# -V1.net
KiCad netlist of a schematic drawn in Altium Designer
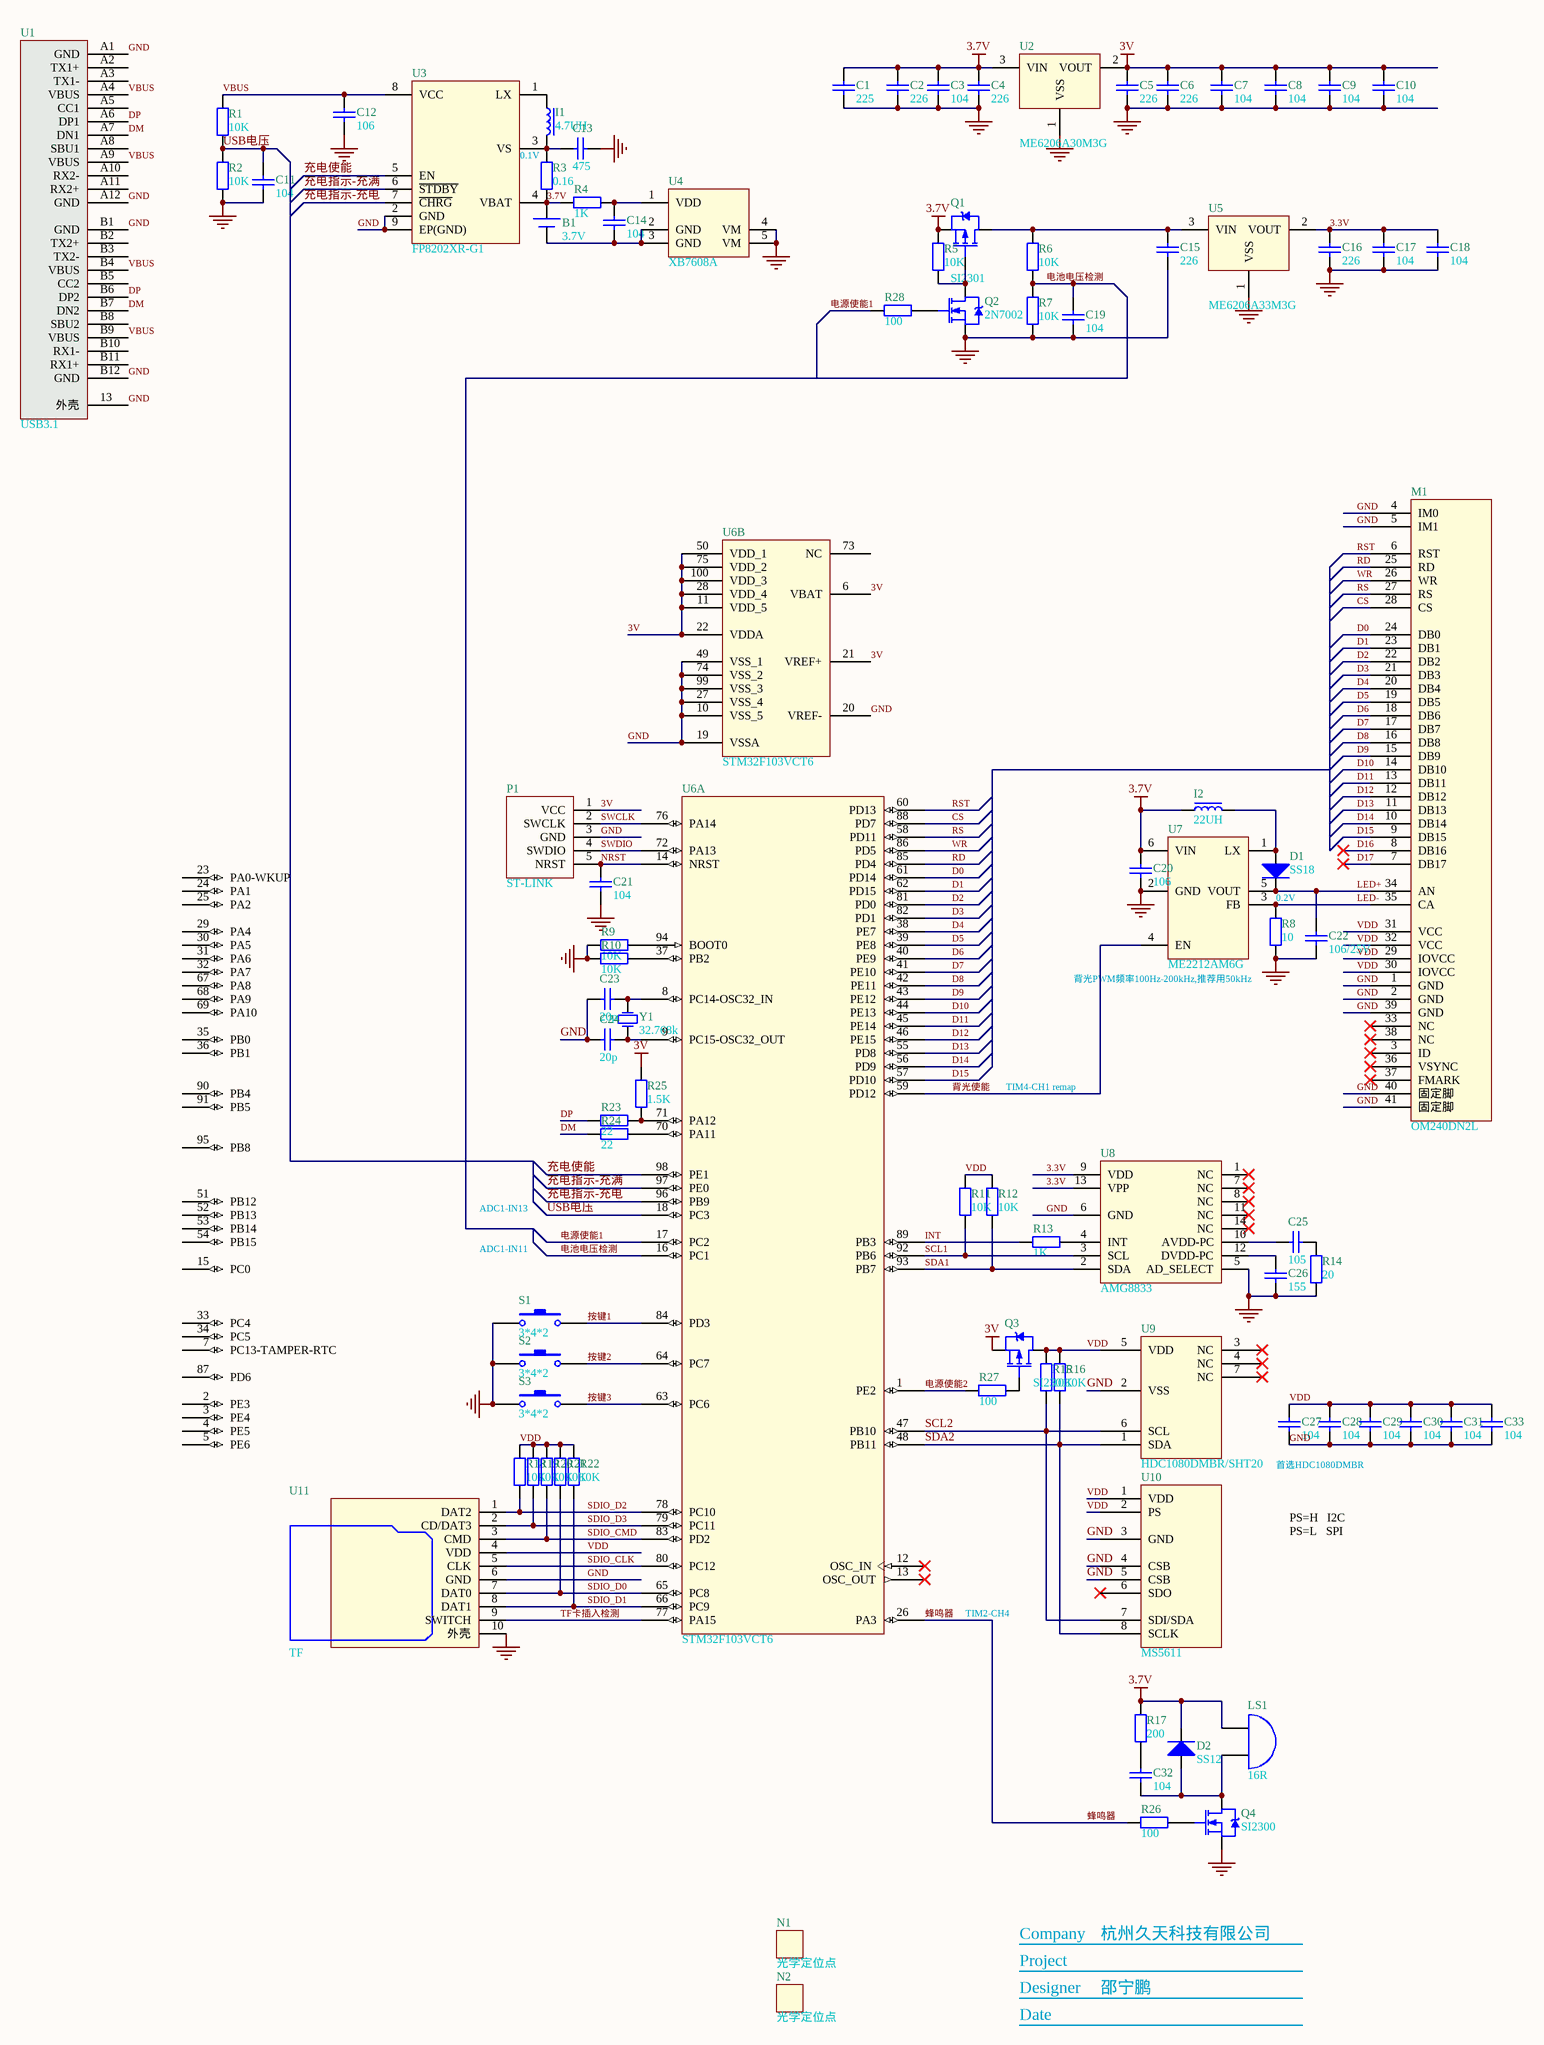
[diagram p0: 红外热像仪-V1.SchDoc]

(export (version "E")
  (design (tool "Eeschema 10.0.6"))
  (components
    (comp (ref "B1")
      (value "3.7V")
      (footprint "PH2.0-卧式贴片-2P")
      (description "锂电池")
      (libsource (lib "11其他元件-V1.0") (part "Battery1"))
    )
    (comp (ref "C1")
      (value "225")
      (footprint "C-0603")
      (description "0805")
      (fields (field (name "PUBLISHER") "Altium Limited"))
      (libsource (lib "2电容-V1.0") (part "Cap-0603"))
    )
    (comp (ref "C2")
      (value "226")
      (footprint "C-0603")
      (description "0805")
      (fields (field (name "PUBLISHER") "Altium Limited"))
      (libsource (lib "2电容-V1.0") (part "Cap-0603"))
    )
    (comp (ref "C3")
      (value "104")
      (footprint "C-0603")
      (description "0805")
      (fields (field (name "PUBLISHER") "Altium Limited"))
      (libsource (lib "2电容-V1.0") (part "Cap-0603"))
    )
    (comp (ref "C4")
      (value "226")
      (footprint "C-0603")
      (description "0805")
      (fields (field (name "PUBLISHER") "Altium Limited"))
      (libsource (lib "2电容-V1.0") (part "Cap-0603"))
    )
    (comp (ref "C5")
      (value "226")
      (footprint "C-0603")
      (description "0805")
      (fields (field (name "PUBLISHER") "Altium Limited"))
      (libsource (lib "2电容-V1.0") (part "Cap-0603"))
    )
    (comp (ref "C6")
      (value "226")
      (footprint "C-0603")
      (description "0805")
      (fields (field (name "PUBLISHER") "Altium Limited"))
      (libsource (lib "2电容-V1.0") (part "Cap-0603"))
    )
    (comp (ref "C7")
      (value "104")
      (footprint "C-0603")
      (description "0805")
      (fields (field (name "PUBLISHER") "Altium Limited"))
      (libsource (lib "2电容-V1.0") (part "Cap-0603"))
    )
    (comp (ref "C8")
      (value "104")
      (footprint "C-0603")
      (description "0805")
      (fields (field (name "PUBLISHER") "Altium Limited"))
      (libsource (lib "2电容-V1.0") (part "Cap-0603"))
    )
    (comp (ref "C9")
      (value "104")
      (footprint "C-0603")
      (description "0805")
      (fields (field (name "PUBLISHER") "Altium Limited"))
      (libsource (lib "2电容-V1.0") (part "Cap-0603"))
    )
    (comp (ref "C10")
      (value "104")
      (footprint "C-0603")
      (description "0805")
      (fields (field (name "PUBLISHER") "Altium Limited"))
      (libsource (lib "2电容-V1.0") (part "Cap-0603"))
    )
    (comp (ref "C11")
      (value "104")
      (footprint "C-0603")
      (description "0805")
      (fields (field (name "PUBLISHER") "Altium Limited"))
      (libsource (lib "2电容-V1.0") (part "Cap-0603"))
    )
    (comp (ref "C12")
      (value "106")
      (footprint "C-0603")
      (description "0805")
      (fields (field (name "PUBLISHER") "Altium Limited"))
      (libsource (lib "2电容-V1.0") (part "Cap-0603"))
    )
    (comp (ref "C13")
      (value "475")
      (footprint "C-0603")
      (description "0805")
      (fields (field (name "PUBLISHER") "Altium Limited"))
      (libsource (lib "2电容-V1.0") (part "Cap-0603"))
    )
    (comp (ref "C14")
      (value "104")
      (footprint "C-0603")
      (description "0805")
      (fields (field (name "PUBLISHER") "Altium Limited"))
      (libsource (lib "2电容-V1.0") (part "Cap-0603"))
    )
    (comp (ref "C15")
      (value "226")
      (footprint "C-0603")
      (description "0805")
      (fields (field (name "PUBLISHER") "Altium Limited"))
      (libsource (lib "2电容-V1.0") (part "Cap-0603"))
    )
    (comp (ref "C16")
      (value "226")
      (footprint "C-0603")
      (description "0805")
      (fields (field (name "PUBLISHER") "Altium Limited"))
      (libsource (lib "2电容-V1.0") (part "Cap-0603"))
    )
    (comp (ref "C17")
      (value "104")
      (footprint "C-0603")
      (description "0805")
      (fields (field (name "PUBLISHER") "Altium Limited"))
      (libsource (lib "2电容-V1.0") (part "Cap-0603"))
    )
    (comp (ref "C18")
      (value "104")
      (footprint "C-0603")
      (description "0805")
      (fields (field (name "PUBLISHER") "Altium Limited"))
      (libsource (lib "2电容-V1.0") (part "Cap-0603"))
    )
    (comp (ref "C19")
      (value "104")
      (footprint "C-0603")
      (description "0805")
      (fields (field (name "PUBLISHER") "Altium Limited"))
      (libsource (lib "2电容-V1.0") (part "Cap-0603"))
    )
    (comp (ref "C20")
      (value "106")
      (footprint "C-0603")
      (description "0805")
      (fields (field (name "PUBLISHER") "Altium Limited"))
      (libsource (lib "2电容-V1.0") (part "Cap-0603"))
    )
    (comp (ref "C21")
      (value "104")
      (footprint "C-0603")
      (description "0805")
      (fields (field (name "PUBLISHER") "Altium Limited"))
      (libsource (lib "2电容-V1.0") (part "Cap-0603"))
    )
    (comp (ref "C22")
      (value "106/25V")
      (footprint "C-0603")
      (description "0805")
      (fields (field (name "PUBLISHER") "Altium Limited"))
      (libsource (lib "2电容-V1.0") (part "Cap-0603"))
    )
    (comp (ref "C23")
      (value "20p")
      (footprint "C-0603")
      (description "0805")
      (fields (field (name "PUBLISHER") "Altium Limited"))
      (libsource (lib "2电容-V1.0") (part "Cap-0603"))
    )
    (comp (ref "C24")
      (value "20p")
      (footprint "C-0603")
      (description "0805")
      (fields (field (name "PUBLISHER") "Altium Limited"))
      (libsource (lib "2电容-V1.0") (part "Cap-0603"))
    )
    (comp (ref "C25")
      (value "105")
      (footprint "C-0603")
      (description "0805")
      (fields (field (name "PUBLISHER") "Altium Limited"))
      (libsource (lib "2电容-V1.0") (part "Cap-0603"))
    )
    (comp (ref "C26")
      (value "155")
      (footprint "C-0603")
      (description "0805")
      (fields (field (name "PUBLISHER") "Altium Limited"))
      (libsource (lib "2电容-V1.0") (part "Cap-0603"))
    )
    (comp (ref "C27")
      (value "104")
      (footprint "C-0603")
      (description "0805")
      (fields (field (name "PUBLISHER") "Altium Limited"))
      (libsource (lib "2电容-V1.0") (part "Cap-0603"))
    )
    (comp (ref "C28")
      (value "104")
      (footprint "C-0603")
      (description "0805")
      (fields (field (name "PUBLISHER") "Altium Limited"))
      (libsource (lib "2电容-V1.0") (part "Cap-0603"))
    )
    (comp (ref "C29")
      (value "104")
      (footprint "C-0603")
      (description "0805")
      (fields (field (name "PUBLISHER") "Altium Limited"))
      (libsource (lib "2电容-V1.0") (part "Cap-0603"))
    )
    (comp (ref "C30")
      (value "104")
      (footprint "C-0603")
      (description "0805")
      (fields (field (name "PUBLISHER") "Altium Limited"))
      (libsource (lib "2电容-V1.0") (part "Cap-0603"))
    )
    (comp (ref "C31")
      (value "104")
      (footprint "C-0603")
      (description "0805")
      (fields (field (name "PUBLISHER") "Altium Limited"))
      (libsource (lib "2电容-V1.0") (part "Cap-0603"))
    )
    (comp (ref "C32")
      (value "104")
      (footprint "C-0603")
      (description "0805")
      (fields (field (name "PUBLISHER") "Altium Limited"))
      (libsource (lib "2电容-V1.0") (part "Cap-0603"))
    )
    (comp (ref "C33")
      (value "104")
      (footprint "C-0603")
      (description "0805")
      (fields (field (name "PUBLISHER") "Altium Limited"))
      (libsource (lib "2电容-V1.0") (part "Cap-0603"))
    )
    (comp (ref "D1")
      (value "SS18")
      (footprint "SOD-523/0603")
      (description "SMA")
      (libsource (lib "4二极管-V1.1") (part "SS14"))
    )
    (comp (ref "D2")
      (value "SS12")
      (footprint "SOD-523/0603")
      (description "SMA")
      (libsource (lib "4二极管-V1.1") (part "SS14"))
    )
    (comp (ref "I1")
      (value "4.7UH")
      (footprint "一体成型电感0420")
      (libsource (lib "3电感-V1.0") (part "Inductance3"))
    )
    (comp (ref "I2") (value "22UH") (footprint "PRS3015") (libsource (lib "3电感-V1.0") (part "Inductance3")))
    (comp (ref "LS1")
      (value "16R")
      (footprint "蜂鸣器DET402-G-1")
      (description "Electrical Bell")
      (fields (field (name "PUBLISHER") "Altium Limited"))
      (libsource (lib "11其他元件-V1.0") (part "Bell"))
    )
    (comp (ref "M1")
      (value "OM240DN2L")
      (footprint "OM240DN2L")
      (libsource (lib "7显示屏-V1.0") (part "OM240DN2L"))
    )
    (comp (ref "N1") (value "光学定位点") (footprint "MARK-1mm-3mm") (libsource (lib "11其他元件-V1.0") (part "无引脚")))
    (comp (ref "N2") (value "光学定位点") (footprint "MARK-1mm-3mm") (libsource (lib "11其他元件-V1.0") (part "无引脚")))
    (comp (ref "P1") (value "ST-LINK") (footprint "5P下载口") (libsource (lib "下载口") (part "ST-LINK-STM32")))
    (comp (ref "Q1")
      (value "SI2301")
      (footprint "SOT-23")
      (description "SOT-23")
      (libsource (lib "4二极管-V1.1") (part "SI2301"))
    )
    (comp (ref "Q2") (value "2N7002") (footprint "SOT-23") (libsource (lib "4二极管-V1.1") (part "2N7002")))
    (comp (ref "Q3")
      (value "SI2301")
      (footprint "SOT-23")
      (description "SOT-23")
      (libsource (lib "4二极管-V1.1") (part "SI2301"))
    )
    (comp (ref "Q4") (value "SI2300") (footprint "SOT-23") (libsource (lib "4二极管-V1.1") (part "2N7002")))
    (comp (ref "R1")
      (value "10K")
      (footprint "R-0603")
      (description "0805")
      (fields (field (name "PUBLISHER") "Altium Limited"))
      (libsource (lib "") (part "Res2_2"))
    )
    (comp (ref "R2")
      (value "10K")
      (footprint "R-0603")
      (description "0805")
      (fields (field (name "PUBLISHER") "Altium Limited"))
      (libsource (lib "") (part "Res2_2"))
    )
    (comp (ref "R3")
      (value "0.16")
      (footprint "R-1206-M")
      (description "0603")
      (fields (field (name "PUBLISHER") "Altium Limited"))
      (libsource (lib "") (part "Res2-0603_2"))
    )
    (comp (ref "R4")
      (value "1K")
      (footprint "R-0603")
      (description "0603")
      (fields (field (name "PUBLISHER") "Altium Limited"))
      (libsource (lib "") (part "Res2-0603_1"))
    )
    (comp (ref "R5")
      (value "10K")
      (footprint "R-0603")
      (description "0805")
      (fields (field (name "PUBLISHER") "Altium Limited"))
      (libsource (lib "") (part "Res2_2"))
    )
    (comp (ref "R6")
      (value "10K")
      (footprint "R-0603")
      (description "0805")
      (fields (field (name "PUBLISHER") "Altium Limited"))
      (libsource (lib "") (part "Res2_1"))
    )
    (comp (ref "R7")
      (value "10K")
      (footprint "R-0603")
      (description "0805")
      (fields (field (name "PUBLISHER") "Altium Limited"))
      (libsource (lib "") (part "Res2_1"))
    )
    (comp (ref "R8")
      (value "10")
      (footprint "R-0603")
      (description "0805")
      (fields (field (name "PUBLISHER") "Altium Limited"))
      (libsource (lib "") (part "Res2_1"))
    )
    (comp (ref "R9")
      (value "10K")
      (footprint "R-0603")
      (description "0603")
      (fields (field (name "PUBLISHER") "Altium Limited"))
      (libsource (lib "") (part "Res2-0603-_3"))
    )
    (comp (ref "R10")
      (value "10K")
      (footprint "R-0603")
      (description "0603")
      (fields (field (name "PUBLISHER") "Altium Limited"))
      (libsource (lib "") (part "Res2-0603-_3"))
    )
    (comp (ref "R11")
      (value "10K")
      (footprint "R-0603")
      (description "0603")
      (fields (field (name "PUBLISHER") "Altium Limited"))
      (libsource (lib "") (part "Res2-0603-_1"))
    )
    (comp (ref "R12")
      (value "10K")
      (footprint "R-0603")
      (description "0603")
      (fields (field (name "PUBLISHER") "Altium Limited"))
      (libsource (lib "") (part "Res2-0603-_1"))
    )
    (comp (ref "R13")
      (value "1K")
      (footprint "R-0603")
      (description "0805")
      (fields (field (name "PUBLISHER") "Altium Limited"))
      (libsource (lib "1电阻-V1.0") (part "Res2"))
    )
    (comp (ref "R14")
      (value "20")
      (footprint "R-0603")
      (description "0603")
      (fields (field (name "PUBLISHER") "Altium Limited"))
      (libsource (lib "") (part "Res2-0603-_1"))
    )
    (comp (ref "R15")
      (value "10K")
      (footprint "R-0603")
      (description "0603")
      (fields (field (name "PUBLISHER") "Altium Limited"))
      (libsource (lib "") (part "Res2-0603-_2"))
    )
    (comp (ref "R16")
      (value "10K")
      (footprint "R-0603")
      (description "0603")
      (fields (field (name "PUBLISHER") "Altium Limited"))
      (libsource (lib "") (part "Res2-0603-_2"))
    )
    (comp (ref "R17")
      (value "200")
      (footprint "R-0603")
      (description "0603")
      (fields (field (name "PUBLISHER") "Altium Limited"))
      (libsource (lib "") (part "Res2-0603-_2"))
    )
    (comp (ref "R18")
      (value "10K")
      (footprint "R-0603")
      (description "0603")
      (fields (field (name "PUBLISHER") "Altium Limited"))
      (libsource (lib "1电阻-V1.0") (part "Res2-0603"))
    )
    (comp (ref "R19")
      (value "10K")
      (footprint "R-0603")
      (description "0603")
      (fields (field (name "PUBLISHER") "Altium Limited"))
      (libsource (lib "1电阻-V1.0") (part "Res2-0603"))
    )
    (comp (ref "R20")
      (value "10K")
      (footprint "R-0603")
      (description "0603")
      (fields (field (name "PUBLISHER") "Altium Limited"))
      (libsource (lib "1电阻-V1.0") (part "Res2-0603"))
    )
    (comp (ref "R21")
      (value "10K")
      (footprint "R-0603")
      (description "0603")
      (fields (field (name "PUBLISHER") "Altium Limited"))
      (libsource (lib "1电阻-V1.0") (part "Res2-0603"))
    )
    (comp (ref "R22")
      (value "10K")
      (footprint "R-0603")
      (description "0603")
      (fields (field (name "PUBLISHER") "Altium Limited"))
      (libsource (lib "1电阻-V1.0") (part "Res2-0603"))
    )
    (comp (ref "R23")
      (value "22")
      (footprint "R-0603")
      (description "0603")
      (fields (field (name "PUBLISHER") "Altium Limited"))
      (libsource (lib "1电阻-V1.0") (part "Res2-0603-"))
    )
    (comp (ref "R24")
      (value "22")
      (footprint "R-0603")
      (description "0603")
      (fields (field (name "PUBLISHER") "Altium Limited"))
      (libsource (lib "1电阻-V1.0") (part "Res2-0603-"))
    )
    (comp (ref "R25")
      (value "1.5K")
      (footprint "R-0603")
      (description "0603")
      (fields (field (name "PUBLISHER") "Altium Limited"))
      (libsource (lib "") (part "Res2-0603-_1"))
    )
    (comp (ref "R26")
      (value "100")
      (footprint "R-0603")
      (description "0603")
      (fields (field (name "PUBLISHER") "Altium Limited"))
      (libsource (lib "") (part "Res2-0603-_3"))
    )
    (comp (ref "R27")
      (value "100")
      (footprint "R-0603")
      (description "0603")
      (fields (field (name "PUBLISHER") "Altium Limited"))
      (libsource (lib "1电阻-V1.0") (part "Res2-0603-"))
    )
    (comp (ref "R28")
      (value "100")
      (footprint "R-0603")
      (description "0603")
      (fields (field (name "PUBLISHER") "Altium Limited"))
      (libsource (lib "1电阻-V1.0") (part "Res2-0603-"))
    )
    (comp (ref "S1")
      (value "3*4*2")
      (footprint "SB-3*4*2")
      (description "SB-6*6*10")
      (fields (field (name "PUBLISHER") "Altium Limited"))
      (libsource (lib "开关-V1") (part "SB-6*6*9"))
    )
    (comp (ref "S2")
      (value "3*4*2")
      (footprint "SB-3*4*2")
      (description "SB-6*6*10")
      (fields (field (name "PUBLISHER") "Altium Limited"))
      (libsource (lib "开关-V1") (part "SB-6*6*9"))
    )
    (comp (ref "S3")
      (value "3*4*2")
      (footprint "SB-3*4*2")
      (description "SB-6*6*10")
      (fields (field (name "PUBLISHER") "Altium Limited"))
      (libsource (lib "开关-V1") (part "SB-6*6*9"))
    )
    (comp (ref "U1")
      (value "USB3.1")
      (footprint "USB-TYPE-C-16P-N")
      (libsource (lib "11其他元件-V1.0") (part "USB3.1-2"))
    )
    (comp (ref "U2")
      (value "ME6206A30M3G")
      (footprint "SOT-23")
      (description "LDO稳压 SOT-23")
      (libsource (lib "电源芯片-线性稳压-V1") (part "ME6206A33M3G"))
    )
    (comp (ref "U3")
      (value "FP8202XR-G1")
      (footprint "SOP-8-N+1")
      (description "单节锂电池充电2A")
      (libsource (lib "充电管理电池保护-V1") (part "FP8202XR-G1"))
    )
    (comp (ref "U4") (value "XB7608A") (footprint "CPC5-M") (libsource (lib "充电管理电池保护-V1") (part "XB7608A")))
    (comp (ref "U5")
      (value "ME6206A33M3G")
      (footprint "SOT-23")
      (description "LDO稳压 SOT-23")
      (libsource (lib "电源芯片-线性稳压-V1") (part "ME6206A33M3G"))
    )
    (comp (ref "U6")
      (value "STM32F103VCT6")
      (footprint "LQFP100")
      (libsource (lib "9单片机-V1.0") (part "STM32F103VCT6"))
    )
    (comp (ref "U7")
      (value "ME2212AM6G")
      (footprint "SOT-23-6-M")
      (description "LED升压恒流")
      (libsource (lib "驱动芯片-LED&LCD") (part "ME2212AM6G"))
    )
    (comp (ref "U8") (value "AMG8833") (footprint "AMG8833") (libsource (lib "传感器") (part "AMG8833")))
    (comp (ref "U9")
      (value "HDC1080DMBR/SHT20")
      (footprint "DFN-6-N")
      (description "温湿度传感器")
      (libsource (lib "8集成电路-V1.1") (part "SHT20"))
    )
    (comp (ref "U10")
      (value "MS5611")
      (footprint "MS5611")
      (description "气压传感器")
      (libsource (lib "传感器") (part "MS5611"))
    )
    (comp (ref "U11") (value "TF") (footprint "TF卡座 自弹") (libsource (lib "11其他元件-V1.0") (part "TF卡座-自弹")))
    (comp (ref "Y1") (value "32.768k") (footprint "FC135") (libsource (lib "11其他元件-V1.0") (part "晶振")))
  )
  (nets
    (net (code "1") (name "/3.3V") (class "Default")
      (node (ref "C16") (pin "2") (pinfunction "2_2") (pintype "passive"))
      (node (ref "C17") (pin "2") (pinfunction "2_2") (pintype "passive"))
      (node (ref "C18") (pin "2") (pinfunction "2_2") (pintype "passive"))
      (node (ref "U5") (pin "2") (pinfunction "VOUT_2") (pintype "passive"))
      (node (ref "U8") (pin "13") (pinfunction "VPP_13") (pintype "passive"))
      (node (ref "U8") (pin "9") (pinfunction "VDD_9") (pintype "passive"))
    )
    (net (code "2") (name "/CS") (class "Default")
      (node (ref "M1") (pin "28") (pinfunction "CS_28") (pintype "passive"))
      (node (ref "U6") (pin "88") (pinfunction "PD7_88") (pintype "bidirectional"))
    )
    (net (code "3") (name "/D0") (class "Default")
      (node (ref "M1") (pin "24") (pinfunction "DB0_24") (pintype "passive"))
      (node (ref "U6") (pin "61") (pinfunction "PD14_61") (pintype "bidirectional"))
    )
    (net (code "4") (name "/D1") (class "Default")
      (node (ref "M1") (pin "23") (pinfunction "DB1_23") (pintype "passive"))
      (node (ref "U6") (pin "62") (pinfunction "PD15_62") (pintype "bidirectional"))
    )
    (net (code "5") (name "/D2") (class "Default")
      (node (ref "M1") (pin "22") (pinfunction "DB2_22") (pintype "passive"))
      (node (ref "U6") (pin "81") (pinfunction "PD0_81") (pintype "bidirectional"))
    )
    (net (code "6") (name "/D3") (class "Default")
      (node (ref "M1") (pin "21") (pinfunction "DB3_21") (pintype "passive"))
      (node (ref "U6") (pin "82") (pinfunction "PD1_82") (pintype "bidirectional"))
    )
    (net (code "7") (name "/D4") (class "Default")
      (node (ref "M1") (pin "20") (pinfunction "DB4_20") (pintype "passive"))
      (node (ref "U6") (pin "38") (pinfunction "PE7_38") (pintype "bidirectional"))
    )
    (net (code "8") (name "/D5") (class "Default")
      (node (ref "M1") (pin "19") (pinfunction "DB5_19") (pintype "passive"))
      (node (ref "U6") (pin "39") (pinfunction "PE8_39") (pintype "bidirectional"))
    )
    (net (code "9") (name "/D6") (class "Default")
      (node (ref "M1") (pin "18") (pinfunction "DB6_18") (pintype "passive"))
      (node (ref "U6") (pin "40") (pinfunction "PE9_40") (pintype "bidirectional"))
    )
    (net (code "10") (name "/D7") (class "Default")
      (node (ref "M1") (pin "17") (pinfunction "DB7_17") (pintype "passive"))
      (node (ref "U6") (pin "41") (pinfunction "PE10_41") (pintype "bidirectional"))
    )
    (net (code "11") (name "/D8") (class "Default")
      (node (ref "M1") (pin "16") (pinfunction "DB8_16") (pintype "passive"))
      (node (ref "U6") (pin "42") (pinfunction "PE11_42") (pintype "bidirectional"))
    )
    (net (code "12") (name "/D9") (class "Default")
      (node (ref "M1") (pin "15") (pinfunction "DB9_15") (pintype "passive"))
      (node (ref "U6") (pin "43") (pinfunction "PE12_43") (pintype "bidirectional"))
    )
    (net (code "13") (name "/D10") (class "Default")
      (node (ref "M1") (pin "14") (pinfunction "DB10_14") (pintype "passive"))
      (node (ref "U6") (pin "44") (pinfunction "PE13_44") (pintype "bidirectional"))
    )
    (net (code "14") (name "/D11") (class "Default")
      (node (ref "M1") (pin "13") (pinfunction "DB11_13") (pintype "passive"))
      (node (ref "U6") (pin "45") (pinfunction "PE14_45") (pintype "bidirectional"))
    )
    (net (code "15") (name "/D12") (class "Default")
      (node (ref "M1") (pin "12") (pinfunction "DB12_12") (pintype "passive"))
      (node (ref "U6") (pin "46") (pinfunction "PE15_46") (pintype "bidirectional"))
    )
    (net (code "16") (name "/D13") (class "Default")
      (node (ref "M1") (pin "11") (pinfunction "DB13_11") (pintype "passive"))
      (node (ref "U6") (pin "55") (pinfunction "PD8_55") (pintype "bidirectional"))
    )
    (net (code "17") (name "/D14") (class "Default")
      (node (ref "M1") (pin "10") (pinfunction "DB14_10") (pintype "passive"))
      (node (ref "U6") (pin "56") (pinfunction "PD9_56") (pintype "bidirectional"))
    )
    (net (code "18") (name "/D15") (class "Default")
      (node (ref "M1") (pin "9") (pinfunction "DB15_9") (pintype "passive"))
      (node (ref "U6") (pin "57") (pinfunction "PD10_57") (pintype "bidirectional"))
    )
    (net (code "19") (name "/D16") (class "Default")
      (node (ref "M1") (pin "8") (pinfunction "DB16_8") (pintype "passive+no_connect"))
    )
    (net (code "20") (name "/D17") (class "Default")
      (node (ref "M1") (pin "7") (pinfunction "DB17_7") (pintype "passive+no_connect"))
    )
    (net (code "21") (name "/DM") (class "Default")
      (node (ref "R24") (pin "1") (pinfunction "1_1") (pintype "passive"))
      (node (ref "U1") (pin "A7") (pinfunction "DN1_A7") (pintype "passive"))
      (node (ref "U1") (pin "B7") (pinfunction "DN2_B7") (pintype "passive"))
    )
    (net (code "22") (name "/DP") (class "Default")
      (node (ref "R23") (pin "1") (pinfunction "1_1") (pintype "passive"))
      (node (ref "U1") (pin "A6") (pinfunction "DP1_A6") (pintype "passive"))
      (node (ref "U1") (pin "B6") (pinfunction "DP2_B6") (pintype "passive"))
    )
    (net (code "23") (name "/INT") (class "Default")
      (node (ref "R13") (pin "2") (pinfunction "2_2") (pintype "passive"))
      (node (ref "U6") (pin "89") (pinfunction "PB3_89") (pintype "bidirectional"))
    )
    (net (code "24") (name "/LED+") (class "Default")
      (node (ref "C22") (pin "2") (pinfunction "2_2") (pintype "passive"))
      (node (ref "D1") (pin "2") (pinfunction "K_2") (pintype "passive"))
      (node (ref "M1") (pin "34") (pinfunction "AN_34") (pintype "passive"))
      (node (ref "U7") (pin "5") (pinfunction "VOUT_5") (pintype "passive"))
    )
    (net (code "25") (name "/LED-") (class "Default")
      (node (ref "M1") (pin "35") (pinfunction "CA_35") (pintype "passive"))
      (node (ref "R8") (pin "2") (pinfunction "2_2") (pintype "passive"))
      (node (ref "U7") (pin "3") (pinfunction "FB_3") (pintype "passive"))
    )
    (net (code "26") (name "/NRST") (class "Default")
      (node (ref "C21") (pin "2") (pinfunction "2_2") (pintype "passive"))
      (node (ref "P1") (pin "5") (pinfunction "NRST_5") (pintype "passive"))
      (node (ref "U6") (pin "14") (pinfunction "NRST_14") (pintype "bidirectional"))
    )
    (net (code "27") (name "/RD") (class "Default")
      (node (ref "M1") (pin "25") (pinfunction "RD_25") (pintype "passive"))
      (node (ref "U6") (pin "85") (pinfunction "PD4_85") (pintype "bidirectional"))
    )
    (net (code "28") (name "/RS") (class "Default")
      (node (ref "M1") (pin "27") (pinfunction "RS_27") (pintype "passive"))
      (node (ref "U6") (pin "58") (pinfunction "PD11_58") (pintype "bidirectional"))
    )
    (net (code "29") (name "/RST") (class "Default")
      (node (ref "M1") (pin "6") (pinfunction "RST_6") (pintype "passive"))
      (node (ref "U6") (pin "60") (pinfunction "PD13_60") (pintype "bidirectional"))
    )
    (net (code "30") (name "/SCL1") (class "Default")
      (node (ref "R11") (pin "2") (pinfunction "2_2") (pintype "passive"))
      (node (ref "U6") (pin "92") (pinfunction "PB6_92") (pintype "bidirectional"))
      (node (ref "U8") (pin "3") (pinfunction "SCL_3") (pintype "passive"))
    )
    (net (code "31") (name "/SCL2") (class "Default")
      (node (ref "R15") (pin "1") (pinfunction "1_1") (pintype "passive"))
      (node (ref "U10") (pin "7") (pinfunction "SDI/SDA_7") (pintype "passive"))
      (node (ref "U6") (pin "47") (pinfunction "PB10_47") (pintype "bidirectional"))
      (node (ref "U9") (pin "6") (pinfunction "SCL_6") (pintype "passive"))
    )
    (net (code "32") (name "/SDA1") (class "Default")
      (node (ref "R12") (pin "2") (pinfunction "2_2") (pintype "passive"))
      (node (ref "U6") (pin "93") (pinfunction "PB7_93") (pintype "bidirectional"))
      (node (ref "U8") (pin "2") (pinfunction "SDA_2") (pintype "passive"))
    )
    (net (code "33") (name "/SDA2") (class "Default")
      (node (ref "R16") (pin "1") (pinfunction "1_1") (pintype "passive"))
      (node (ref "U10") (pin "8") (pinfunction "SCLK_8") (pintype "passive"))
      (node (ref "U6") (pin "48") (pinfunction "PB11_48") (pintype "bidirectional"))
      (node (ref "U9") (pin "1") (pinfunction "SDA_1") (pintype "passive"))
    )
    (net (code "34") (name "/SDIO_CLK") (class "Default")
      (node (ref "U11") (pin "5") (pinfunction "CLK_5") (pintype "passive"))
      (node (ref "U6") (pin "80") (pinfunction "PC12_80") (pintype "bidirectional"))
    )
    (net (code "35") (name "/SDIO_CMD") (class "Default")
      (node (ref "R20") (pin "2") (pinfunction "2_2") (pintype "passive"))
      (node (ref "U11") (pin "3") (pinfunction "CMD_3") (pintype "passive"))
      (node (ref "U6") (pin "83") (pinfunction "PD2_83") (pintype "bidirectional"))
    )
    (net (code "36") (name "/SDIO_D0") (class "Default")
      (node (ref "R21") (pin "2") (pinfunction "2_2") (pintype "passive"))
      (node (ref "U11") (pin "7") (pinfunction "DAT0_7") (pintype "passive"))
      (node (ref "U6") (pin "65") (pinfunction "PC8_65") (pintype "bidirectional"))
    )
    (net (code "37") (name "/SDIO_D1") (class "Default")
      (node (ref "R22") (pin "2") (pinfunction "2_2") (pintype "passive"))
      (node (ref "U11") (pin "8") (pinfunction "DAT1_8") (pintype "passive"))
      (node (ref "U6") (pin "66") (pinfunction "PC9_66") (pintype "bidirectional"))
    )
    (net (code "38") (name "/SDIO_D2") (class "Default")
      (node (ref "R18") (pin "2") (pinfunction "2_2") (pintype "passive"))
      (node (ref "U11") (pin "1") (pinfunction "DAT2_1") (pintype "passive"))
      (node (ref "U6") (pin "78") (pinfunction "PC10_78") (pintype "bidirectional"))
    )
    (net (code "39") (name "/SDIO_D3") (class "Default")
      (node (ref "R19") (pin "2") (pinfunction "2_2") (pintype "passive"))
      (node (ref "U11") (pin "2") (pinfunction "CD/DAT3_2") (pintype "passive"))
      (node (ref "U6") (pin "79") (pinfunction "PC11_79") (pintype "bidirectional"))
    )
    (net (code "40") (name "/SWCLK") (class "Default")
      (node (ref "P1") (pin "2") (pinfunction "SWCLK_2") (pintype "passive"))
      (node (ref "U6") (pin "76") (pinfunction "PA14_76") (pintype "bidirectional"))
    )
    (net (code "41") (name "/SWDIO") (class "Default")
      (node (ref "P1") (pin "4") (pinfunction "SWDIO_4") (pintype "passive"))
      (node (ref "U6") (pin "72") (pinfunction "PA13_72") (pintype "bidirectional"))
    )
    (net (code "42") (name "/TF卡插入检测") (class "Default")
      (node (ref "U11") (pin "9") (pinfunction "SWITCH_9") (pintype "passive"))
      (node (ref "U6") (pin "77") (pinfunction "PA15_77") (pintype "bidirectional"))
    )
    (net (code "43") (name "/USB电压") (class "Default")
      (node (ref "C11") (pin "2") (pinfunction "2_2") (pintype "passive"))
      (node (ref "R1") (pin "1") (pinfunction "1_1") (pintype "passive"))
      (node (ref "R2") (pin "2") (pinfunction "2_2") (pintype "passive"))
      (node (ref "U6") (pin "18") (pinfunction "PC3_18") (pintype "bidirectional"))
    )
    (net (code "44") (name "/VBUS") (class "Default")
      (node (ref "C12") (pin "2") (pinfunction "2_2") (pintype "passive"))
      (node (ref "R1") (pin "2") (pinfunction "2_2") (pintype "passive"))
      (node (ref "U1") (pin "A4") (pinfunction "VBUS_A4") (pintype "passive"))
      (node (ref "U1") (pin "A9") (pinfunction "VBUS_A9") (pintype "passive"))
      (node (ref "U1") (pin "B4") (pinfunction "VBUS_B4") (pintype "passive"))
      (node (ref "U1") (pin "B9") (pinfunction "VBUS_B9") (pintype "passive"))
      (node (ref "U3") (pin "8") (pinfunction "VCC_8") (pintype "passive"))
    )
    (net (code "45") (name "/VDD") (class "Default")
      (node (ref "C27") (pin "2") (pinfunction "2_2") (pintype "passive"))
      (node (ref "C28") (pin "2") (pinfunction "2_2") (pintype "passive"))
      (node (ref "C29") (pin "2") (pinfunction "2_2") (pintype "passive"))
      (node (ref "C30") (pin "2") (pinfunction "2_2") (pintype "passive"))
      (node (ref "C31") (pin "2") (pinfunction "2_2") (pintype "passive"))
      (node (ref "C33") (pin "2") (pinfunction "2_2") (pintype "passive"))
      (node (ref "M1") (pin "29") (pinfunction "IOVCC_29") (pintype "passive"))
      (node (ref "M1") (pin "30") (pinfunction "IOVCC_30") (pintype "passive"))
      (node (ref "M1") (pin "31") (pinfunction "VCC_31") (pintype "passive"))
      (node (ref "M1") (pin "32") (pinfunction "VCC_32") (pintype "passive"))
      (node (ref "Q3") (pin "3") (pinfunction "D_3") (pintype "passive"))
      (node (ref "R11") (pin "1") (pinfunction "1_1") (pintype "passive"))
      (node (ref "R12") (pin "1") (pinfunction "1_1") (pintype "passive"))
      (node (ref "R15") (pin "2") (pinfunction "2_2") (pintype "passive"))
      (node (ref "R16") (pin "2") (pinfunction "2_2") (pintype "passive"))
      (node (ref "R18") (pin "1") (pinfunction "1_1") (pintype "passive"))
      (node (ref "R19") (pin "1") (pinfunction "1_1") (pintype "passive"))
      (node (ref "R20") (pin "1") (pinfunction "1_1") (pintype "passive"))
      (node (ref "R21") (pin "1") (pinfunction "1_1") (pintype "passive"))
      (node (ref "R22") (pin "1") (pinfunction "1_1") (pintype "passive"))
      (node (ref "U10") (pin "1") (pinfunction "VDD_1") (pintype "passive"))
      (node (ref "U10") (pin "2") (pinfunction "PS_2") (pintype "passive"))
      (node (ref "U11") (pin "4") (pinfunction "VDD_4") (pintype "passive"))
      (node (ref "U9") (pin "5") (pinfunction "VDD_5") (pintype "passive"))
    )
    (net (code "46") (name "/WR") (class "Default")
      (node (ref "M1") (pin "26") (pinfunction "WR_26") (pintype "passive"))
      (node (ref "U6") (pin "86") (pinfunction "PD5_86") (pintype "bidirectional"))
    )
    (net (code "47") (name "/充电使能") (class "Default")
      (node (ref "U3") (pin "5") (pinfunction "EN_5") (pintype "passive"))
      (node (ref "U6") (pin "98") (pinfunction "PE1_98") (pintype "bidirectional"))
    )
    (net (code "48") (name "/充电指示-充满") (class "Default")
      (node (ref "U3") (pin "6") (pinfunction "~{STDBY}_6") (pintype "passive"))
      (node (ref "U6") (pin "97") (pinfunction "PE0_97") (pintype "bidirectional"))
    )
    (net (code "49") (name "/充电指示-充电") (class "Default")
      (node (ref "U3") (pin "7") (pinfunction "~{CHRG}_7") (pintype "passive"))
      (node (ref "U6") (pin "96") (pinfunction "PB9_96") (pintype "bidirectional"))
    )
    (net (code "50") (name "/按键1") (class "Default")
      (node (ref "S1") (pin "1") (pinfunction "1_1") (pintype "passive"))
      (node (ref "U6") (pin "84") (pinfunction "PD3_84") (pintype "bidirectional"))
    )
    (net (code "51") (name "/按键2") (class "Default")
      (node (ref "S2") (pin "2") (pinfunction "2_2") (pintype "passive"))
      (node (ref "U6") (pin "64") (pinfunction "PC7_64") (pintype "bidirectional"))
    )
    (net (code "52") (name "/按键3") (class "Default")
      (node (ref "S3") (pin "1") (pinfunction "1_1") (pintype "passive"))
      (node (ref "U6") (pin "63") (pinfunction "PC6_63") (pintype "bidirectional"))
    )
    (net (code "53") (name "/电池电压检测") (class "Default")
      (node (ref "C19") (pin "2") (pinfunction "2_2") (pintype "passive"))
      (node (ref "R6") (pin "1") (pinfunction "1_1") (pintype "passive"))
      (node (ref "R7") (pin "2") (pinfunction "2_2") (pintype "passive"))
      (node (ref "U6") (pin "16") (pinfunction "PC1_16") (pintype "bidirectional"))
    )
    (net (code "54") (name "/电源使能1") (class "Default")
      (node (ref "R28") (pin "1") (pinfunction "1_1") (pintype "passive"))
      (node (ref "U6") (pin "17") (pinfunction "PC2_17") (pintype "bidirectional"))
    )
    (net (code "55") (name "/电源使能2") (class "Default")
      (node (ref "R27") (pin "1") (pinfunction "1_1") (pintype "passive"))
      (node (ref "U6") (pin "1") (pinfunction "PE2_1") (pintype "bidirectional"))
    )
    (net (code "56") (name "/背光使能") (class "Default")
      (node (ref "U6") (pin "59") (pinfunction "PD12_59") (pintype "bidirectional"))
      (node (ref "U7") (pin "4") (pinfunction "EN_4") (pintype "passive"))
    )
    (net (code "57") (name "/蜂鸣器") (class "Default")
      (node (ref "R26") (pin "2") (pinfunction "2_2") (pintype "passive"))
      (node (ref "U6") (pin "26") (pinfunction "PA3_26") (pintype "bidirectional"))
    )
    (net (code "58") (name "3.7V") (class "Default")
      (node (ref "B1") (pin "2") (pinfunction "-_2") (pintype "passive"))
      (node (ref "C1") (pin "2") (pinfunction "2_2") (pintype "passive"))
      (node (ref "C2") (pin "2") (pinfunction "2_2") (pintype "passive"))
      (node (ref "C20") (pin "1") (pinfunction "1_1") (pintype "passive"))
      (node (ref "C3") (pin "2") (pinfunction "2_2") (pintype "passive"))
      (node (ref "C4") (pin "2") (pinfunction "2_2") (pintype "passive"))
      (node (ref "D2") (pin "2") (pinfunction "K_2") (pintype "passive"))
      (node (ref "I2") (pin "1") (pinfunction "1_1") (pintype "passive"))
      (node (ref "LS1") (pin "1") (pinfunction "A_1") (pintype "passive"))
      (node (ref "Q1") (pin "2") (pinfunction "S_2") (pintype "passive"))
      (node (ref "R17") (pin "2") (pinfunction "2_2") (pintype "passive"))
      (node (ref "R3") (pin "1") (pinfunction "1_1") (pintype "passive"))
      (node (ref "R4") (pin "1") (pinfunction "1_1") (pintype "passive"))
      (node (ref "R5") (pin "2") (pinfunction "2_2") (pintype "passive"))
      (node (ref "U2") (pin "3") (pinfunction "VIN_3") (pintype "passive"))
      (node (ref "U3") (pin "4") (pinfunction "VBAT_4") (pintype "passive"))
      (node (ref "U7") (pin "6") (pinfunction "VIN_6") (pintype "passive"))
    )
    (net (code "59") (name "3V") (class "Default")
      (node (ref "C10") (pin "2") (pinfunction "2_2") (pintype "passive"))
      (node (ref "C5") (pin "2") (pinfunction "2_2") (pintype "passive"))
      (node (ref "C6") (pin "2") (pinfunction "2_2") (pintype "passive"))
      (node (ref "C7") (pin "2") (pinfunction "2_2") (pintype "passive"))
      (node (ref "C8") (pin "2") (pinfunction "2_2") (pintype "passive"))
      (node (ref "C9") (pin "2") (pinfunction "2_2") (pintype "passive"))
      (node (ref "P1") (pin "1") (pinfunction "VCC_1") (pintype "passive"))
      (node (ref "Q3") (pin "2") (pinfunction "S_2") (pintype "passive"))
      (node (ref "R25") (pin "1") (pinfunction "1_1") (pintype "passive"))
      (node (ref "U2") (pin "2") (pinfunction "VOUT_2") (pintype "passive"))
      (node (ref "U6") (pin "100") (pinfunction "VDD_3_100") (pintype "power_in"))
      (node (ref "U6") (pin "11") (pinfunction "VDD_5_11") (pintype "power_in"))
      (node (ref "U6") (pin "21") (pinfunction "VREF+_21") (pintype "power_in"))
      (node (ref "U6") (pin "22") (pinfunction "VDDA_22") (pintype "power_in"))
      (node (ref "U6") (pin "28") (pinfunction "VDD_4_28") (pintype "power_in"))
      (node (ref "U6") (pin "50") (pinfunction "VDD_1_50") (pintype "power_in"))
      (node (ref "U6") (pin "6") (pinfunction "VBAT_6") (pintype "power_in"))
      (node (ref "U6") (pin "75") (pinfunction "VDD_2_75") (pintype "power_in"))
    )
    (net (code "60") (name "GND") (class "Default")
      (node (ref "C1") (pin "1") (pinfunction "1_1") (pintype "passive"))
      (node (ref "C10") (pin "1") (pinfunction "1_1") (pintype "passive"))
      (node (ref "C11") (pin "1") (pinfunction "1_1") (pintype "passive"))
      (node (ref "C12") (pin "1") (pinfunction "1_1") (pintype "passive"))
      (node (ref "C13") (pin "1") (pinfunction "1_1") (pintype "passive"))
      (node (ref "C15") (pin "1") (pinfunction "1_1") (pintype "passive"))
      (node (ref "C16") (pin "1") (pinfunction "1_1") (pintype "passive"))
      (node (ref "C17") (pin "1") (pinfunction "1_1") (pintype "passive"))
      (node (ref "C18") (pin "1") (pinfunction "1_1") (pintype "passive"))
      (node (ref "C19") (pin "1") (pinfunction "1_1") (pintype "passive"))
      (node (ref "C2") (pin "1") (pinfunction "1_1") (pintype "passive"))
      (node (ref "C20") (pin "2") (pinfunction "2_2") (pintype "passive"))
      (node (ref "C21") (pin "1") (pinfunction "1_1") (pintype "passive"))
      (node (ref "C22") (pin "1") (pinfunction "1_1") (pintype "passive"))
      (node (ref "C23") (pin "2") (pinfunction "2_2") (pintype "passive"))
      (node (ref "C24") (pin "2") (pinfunction "2_2") (pintype "passive"))
      (node (ref "C26") (pin "1") (pinfunction "1_1") (pintype "passive"))
      (node (ref "C27") (pin "1") (pinfunction "1_1") (pintype "passive"))
      (node (ref "C28") (pin "1") (pinfunction "1_1") (pintype "passive"))
      (node (ref "C29") (pin "1") (pinfunction "1_1") (pintype "passive"))
      (node (ref "C3") (pin "1") (pinfunction "1_1") (pintype "passive"))
      (node (ref "C30") (pin "1") (pinfunction "1_1") (pintype "passive"))
      (node (ref "C31") (pin "1") (pinfunction "1_1") (pintype "passive"))
      (node (ref "C33") (pin "1") (pinfunction "1_1") (pintype "passive"))
      (node (ref "C4") (pin "1") (pinfunction "1_1") (pintype "passive"))
      (node (ref "C5") (pin "1") (pinfunction "1_1") (pintype "passive"))
      (node (ref "C6") (pin "1") (pinfunction "1_1") (pintype "passive"))
      (node (ref "C7") (pin "1") (pinfunction "1_1") (pintype "passive"))
      (node (ref "C8") (pin "1") (pinfunction "1_1") (pintype "passive"))
      (node (ref "C9") (pin "1") (pinfunction "1_1") (pintype "passive"))
      (node (ref "M1") (pin "1") (pinfunction "GND_1") (pintype "passive"))
      (node (ref "M1") (pin "2") (pinfunction "GND_2") (pintype "passive"))
      (node (ref "M1") (pin "39") (pinfunction "GND_39") (pintype "passive"))
      (node (ref "M1") (pin "4") (pinfunction "IM0_4") (pintype "passive"))
      (node (ref "M1") (pin "40") (pinfunction "固定脚_40") (pintype "passive"))
      (node (ref "M1") (pin "41") (pinfunction "固定脚_41") (pintype "passive"))
      (node (ref "M1") (pin "5") (pinfunction "IM1_5") (pintype "passive"))
      (node (ref "P1") (pin "3") (pinfunction "GND_3") (pintype "passive"))
      (node (ref "Q2") (pin "2") (pinfunction "S_2") (pintype "passive"))
      (node (ref "Q4") (pin "2") (pinfunction "S_2") (pintype "passive"))
      (node (ref "R10") (pin "2") (pinfunction "2_2") (pintype "passive"))
      (node (ref "R14") (pin "2") (pinfunction "2_2") (pintype "passive"))
      (node (ref "R2") (pin "1") (pinfunction "1_1") (pintype "passive"))
      (node (ref "R7") (pin "1") (pinfunction "1_1") (pintype "passive"))
      (node (ref "R8") (pin "1") (pinfunction "1_1") (pintype "passive"))
      (node (ref "R9") (pin "2") (pinfunction "2_2") (pintype "passive"))
      (node (ref "S1") (pin "2") (pinfunction "2_2") (pintype "passive"))
      (node (ref "S2") (pin "1") (pinfunction "1_1") (pintype "passive"))
      (node (ref "S3") (pin "2") (pinfunction "2_2") (pintype "passive"))
      (node (ref "U1") (pin "13") (pinfunction "外壳_13") (pintype "passive"))
      (node (ref "U1") (pin "A1") (pinfunction "GND_A1") (pintype "passive"))
      (node (ref "U1") (pin "A12") (pinfunction "GND_A12") (pintype "passive"))
      (node (ref "U1") (pin "B1") (pinfunction "GND_B1") (pintype "passive"))
      (node (ref "U1") (pin "B12") (pinfunction "GND_B12") (pintype "passive"))
      (node (ref "U10") (pin "3") (pinfunction "GND_3") (pintype "passive"))
      (node (ref "U10") (pin "4") (pinfunction "CSB_4") (pintype "passive"))
      (node (ref "U10") (pin "5") (pinfunction "CSB_5") (pintype "passive"))
      (node (ref "U11") (pin "10") (pinfunction "外壳_10") (pintype "passive"))
      (node (ref "U11") (pin "6") (pinfunction "GND_6") (pintype "passive"))
      (node (ref "U2") (pin "1") (pinfunction "VSS_1") (pintype "passive"))
      (node (ref "U3") (pin "2") (pinfunction "GND_2") (pintype "passive"))
      (node (ref "U3") (pin "9") (pinfunction "EP(GND)_9") (pintype "passive"))
      (node (ref "U4") (pin "4") (pinfunction "VM_4") (pintype "passive"))
      (node (ref "U4") (pin "5") (pinfunction "VM_5") (pintype "passive"))
      (node (ref "U5") (pin "1") (pinfunction "VSS_1") (pintype "passive"))
      (node (ref "U6") (pin "10") (pinfunction "VSS_5_10") (pintype "power_in"))
      (node (ref "U6") (pin "19") (pinfunction "VSSA_19") (pintype "power_in"))
      (node (ref "U6") (pin "20") (pinfunction "VREF-_20") (pintype "power_in"))
      (node (ref "U6") (pin "27") (pinfunction "VSS_4_27") (pintype "power_in"))
      (node (ref "U6") (pin "49") (pinfunction "VSS_1_49") (pintype "power_in"))
      (node (ref "U6") (pin "74") (pinfunction "VSS_2_74") (pintype "power_in"))
      (node (ref "U6") (pin "99") (pinfunction "VSS_3_99") (pintype "power_in"))
      (node (ref "U7") (pin "2") (pinfunction "GND_2") (pintype "passive"))
      (node (ref "U8") (pin "5") (pinfunction "AD_SELECT_5") (pintype "passive"))
      (node (ref "U8") (pin "6") (pinfunction "GND_6") (pintype "passive"))
      (node (ref "U9") (pin "2") (pinfunction "VSS_2") (pintype "passive"))
    )
    (net (code "61") (name "Net-(B1-+)") (class "Default")
      (node (ref "B1") (pin "1") (pinfunction "+_1") (pintype "passive"))
      (node (ref "C14") (pin "1") (pinfunction "1_1") (pintype "passive"))
      (node (ref "U4") (pin "2") (pinfunction "GND_2") (pintype "passive"))
      (node (ref "U4") (pin "3") (pinfunction "GND_3") (pintype "passive"))
    )
    (net (code "62") (name "Net-(C25-Pad1)") (class "Default")
      (node (ref "C25") (pin "1") (pinfunction "1_1") (pintype "passive"))
      (node (ref "R14") (pin "1") (pinfunction "1_1") (pintype "passive"))
    )
    (net (code "63") (name "Net-(C32-Pad2)") (class "Default")
      (node (ref "C32") (pin "2") (pinfunction "2_2") (pintype "passive"))
      (node (ref "R17") (pin "1") (pinfunction "1_1") (pintype "passive"))
    )
    (net (code "64") (name "Net-(D1-A)") (class "Default")
      (node (ref "D1") (pin "1") (pinfunction "A_1") (pintype "passive"))
      (node (ref "I2") (pin "2") (pinfunction "2_2") (pintype "passive"))
      (node (ref "U7") (pin "1") (pinfunction "LX_1") (pintype "passive"))
    )
    (net (code "65") (name "Net-(D2-A)") (class "Default")
      (node (ref "C32") (pin "1") (pinfunction "1_1") (pintype "passive"))
      (node (ref "D2") (pin "1") (pinfunction "A_1") (pintype "passive"))
      (node (ref "LS1") (pin "2") (pinfunction "B_2") (pintype "passive"))
      (node (ref "Q4") (pin "3") (pinfunction "D_3") (pintype "passive"))
    )
    (net (code "66") (name "Net-(Q1-D)") (class "Default")
      (node (ref "C15") (pin "2") (pinfunction "2_2") (pintype "passive"))
      (node (ref "Q1") (pin "3") (pinfunction "D_3") (pintype "passive"))
      (node (ref "R6") (pin "2") (pinfunction "2_2") (pintype "passive"))
      (node (ref "U5") (pin "3") (pinfunction "VIN_3") (pintype "passive"))
    )
    (net (code "67") (name "Net-(Q1-G)") (class "Default")
      (node (ref "Q1") (pin "1") (pinfunction "G_1") (pintype "passive"))
      (node (ref "Q2") (pin "3") (pinfunction "D_3") (pintype "passive"))
      (node (ref "R5") (pin "1") (pinfunction "1_1") (pintype "passive"))
    )
    (net (code "68") (name "Net-(Q2-G)") (class "Default")
      (node (ref "Q2") (pin "1") (pinfunction "G_1") (pintype "passive"))
      (node (ref "R28") (pin "2") (pinfunction "2_2") (pintype "passive"))
    )
    (net (code "69") (name "Net-(Q3-G)") (class "Default")
      (node (ref "Q3") (pin "1") (pinfunction "G_1") (pintype "passive"))
      (node (ref "R27") (pin "2") (pinfunction "2_2") (pintype "passive"))
    )
    (net (code "70") (name "Net-(Q4-G)") (class "Default")
      (node (ref "Q4") (pin "1") (pinfunction "G_1") (pintype "passive"))
      (node (ref "R26") (pin "1") (pinfunction "1_1") (pintype "passive"))
    )
    (net (code "71") (name "Net-(U3-LX)") (class "Default")
      (node (ref "I1") (pin "1") (pinfunction "1_1") (pintype "passive"))
      (node (ref "U3") (pin "1") (pinfunction "LX_1") (pintype "passive"))
    )
    (net (code "72") (name "Net-(U3-VS)") (class "Default")
      (node (ref "C13") (pin "2") (pinfunction "2_2") (pintype "passive"))
      (node (ref "I1") (pin "2") (pinfunction "2_2") (pintype "passive"))
      (node (ref "R3") (pin "2") (pinfunction "2_2") (pintype "passive"))
      (node (ref "U3") (pin "3") (pinfunction "VS_3") (pintype "passive"))
    )
    (net (code "73") (name "Net-(U4-VDD)") (class "Default")
      (node (ref "C14") (pin "2") (pinfunction "2_2") (pintype "passive"))
      (node (ref "R4") (pin "2") (pinfunction "2_2") (pintype "passive"))
      (node (ref "U4") (pin "1") (pinfunction "VDD_1") (pintype "passive"))
    )
    (net (code "74") (name "Net-(U6A-BOOT0)") (class "Default")
      (node (ref "R9") (pin "1") (pinfunction "1_1") (pintype "passive"))
      (node (ref "U6") (pin "94") (pinfunction "BOOT0_94") (pintype "input"))
    )
    (net (code "75") (name "Net-(U6A-PA11)") (class "Default")
      (node (ref "R24") (pin "2") (pinfunction "2_2") (pintype "passive"))
      (node (ref "U6") (pin "70") (pinfunction "PA11_70") (pintype "bidirectional"))
    )
    (net (code "76") (name "Net-(U6A-PA12)") (class "Default")
      (node (ref "R23") (pin "2") (pinfunction "2_2") (pintype "passive"))
      (node (ref "R25") (pin "2") (pinfunction "2_2") (pintype "passive"))
      (node (ref "U6") (pin "71") (pinfunction "PA12_71") (pintype "bidirectional"))
    )
    (net (code "77") (name "Net-(U6A-PB2)") (class "Default")
      (node (ref "R10") (pin "1") (pinfunction "1_1") (pintype "passive"))
      (node (ref "U6") (pin "37") (pinfunction "PB2_37") (pintype "bidirectional"))
    )
    (net (code "78") (name "Net-(U6A-PC14-OSC32_IN)") (class "Default")
      (node (ref "C23") (pin "1") (pinfunction "1_1") (pintype "passive"))
      (node (ref "U6") (pin "8") (pinfunction "PC14-OSC32_IN_8") (pintype "bidirectional"))
      (node (ref "Y1") (pin "2") (pinfunction "OSC2_2") (pintype "passive"))
    )
    (net (code "79") (name "Net-(U6A-PC15-OSC32_OUT)") (class "Default")
      (node (ref "C24") (pin "1") (pinfunction "1_1") (pintype "passive"))
      (node (ref "U6") (pin "9") (pinfunction "PC15-OSC32_OUT_9") (pintype "bidirectional"))
      (node (ref "Y1") (pin "1") (pinfunction "OSC1_1") (pintype "passive"))
    )
    (net (code "80") (name "Net-(U8-AVDD-PC)") (class "Default")
      (node (ref "C25") (pin "2") (pinfunction "2_2") (pintype "passive"))
      (node (ref "U8") (pin "10") (pinfunction "AVDD-PC_10") (pintype "passive"))
    )
    (net (code "81") (name "Net-(U8-DVDD-PC)") (class "Default")
      (node (ref "C26") (pin "2") (pinfunction "2_2") (pintype "passive"))
      (node (ref "U8") (pin "12") (pinfunction "DVDD-PC_12") (pintype "passive"))
    )
    (net (code "82") (name "Net-(U8-INT)") (class "Default")
      (node (ref "R13") (pin "1") (pinfunction "1_1") (pintype "passive"))
      (node (ref "U8") (pin "4") (pinfunction "INT_4") (pintype "passive"))
    )
    (net (code "83") (name "unconnected-(M1-FMARK-Pad37)") (class "Default")
      (node (ref "M1") (pin "37") (pinfunction "FMARK_37") (pintype "passive+no_connect"))
    )
    (net (code "84") (name "unconnected-(M1-ID-Pad3)") (class "Default")
      (node (ref "M1") (pin "3") (pinfunction "ID_3") (pintype "passive+no_connect"))
    )
    (net (code "85") (name "unconnected-(M1-NC-Pad33)") (class "Default")
      (node (ref "M1") (pin "33") (pinfunction "NC_33") (pintype "passive+no_connect"))
    )
    (net (code "86") (name "unconnected-(M1-NC-Pad38)") (class "Default")
      (node (ref "M1") (pin "38") (pinfunction "NC_38") (pintype "passive+no_connect"))
    )
    (net (code "87") (name "unconnected-(M1-VSYNC-Pad36)") (class "Default")
      (node (ref "M1") (pin "36") (pinfunction "VSYNC_36") (pintype "passive+no_connect"))
    )
    (net (code "88") (name "unconnected-(U1-CC1-PadA5)") (class "Default")
      (node (ref "U1") (pin "A5") (pinfunction "CC1_A5") (pintype "passive"))
    )
    (net (code "89") (name "unconnected-(U1-CC2-PadB5)") (class "Default")
      (node (ref "U1") (pin "B5") (pinfunction "CC2_B5") (pintype "passive"))
    )
    (net (code "90") (name "unconnected-(U1-RX1+-PadB11)") (class "Default")
      (node (ref "U1") (pin "B11") (pinfunction "RX1+_B11") (pintype "passive"))
    )
    (net (code "91") (name "unconnected-(U1-RX1--PadB10)") (class "Default")
      (node (ref "U1") (pin "B10") (pinfunction "RX1-_B10") (pintype "passive"))
    )
    (net (code "92") (name "unconnected-(U1-RX2+-PadA11)") (class "Default")
      (node (ref "U1") (pin "A11") (pinfunction "RX2+_A11") (pintype "passive"))
    )
    (net (code "93") (name "unconnected-(U1-RX2--PadA10)") (class "Default")
      (node (ref "U1") (pin "A10") (pinfunction "RX2-_A10") (pintype "passive"))
    )
    (net (code "94") (name "unconnected-(U1-SBU1-PadA8)") (class "Default")
      (node (ref "U1") (pin "A8") (pinfunction "SBU1_A8") (pintype "passive"))
    )
    (net (code "95") (name "unconnected-(U1-SBU2-PadB8)") (class "Default")
      (node (ref "U1") (pin "B8") (pinfunction "SBU2_B8") (pintype "passive"))
    )
    (net (code "96") (name "unconnected-(U1-TX1+-PadA2)") (class "Default")
      (node (ref "U1") (pin "A2") (pinfunction "TX1+_A2") (pintype "passive"))
    )
    (net (code "97") (name "unconnected-(U1-TX1--PadA3)") (class "Default")
      (node (ref "U1") (pin "A3") (pinfunction "TX1-_A3") (pintype "passive"))
    )
    (net (code "98") (name "unconnected-(U1-TX2+-PadB2)") (class "Default")
      (node (ref "U1") (pin "B2") (pinfunction "TX2+_B2") (pintype "passive"))
    )
    (net (code "99") (name "unconnected-(U1-TX2--PadB3)") (class "Default")
      (node (ref "U1") (pin "B3") (pinfunction "TX2-_B3") (pintype "passive"))
    )
    (net (code "100") (name "unconnected-(U6A-OSC_IN-Pad12)") (class "Default")
      (node (ref "U6") (pin "12") (pinfunction "OSC_IN_12") (pintype "input+no_connect"))
    )
    (net (code "101") (name "unconnected-(U6A-OSC_OUT-Pad13)") (class "Default")
      (node (ref "U6") (pin "13") (pinfunction "OSC_OUT_13") (pintype "output+no_connect"))
    )
    (net (code "102") (name "unconnected-(U6A-PA0-WKUP-Pad23)") (class "Default")
      (node (ref "U6") (pin "23") (pinfunction "PA0-WKUP_23") (pintype "bidirectional"))
    )
    (net (code "103") (name "unconnected-(U6A-PA1-Pad24)") (class "Default")
      (node (ref "U6") (pin "24") (pinfunction "PA1_24") (pintype "bidirectional"))
    )
    (net (code "104") (name "unconnected-(U6A-PA2-Pad25)") (class "Default")
      (node (ref "U6") (pin "25") (pinfunction "PA2_25") (pintype "bidirectional"))
    )
    (net (code "105") (name "unconnected-(U6A-PA4-Pad29)") (class "Default")
      (node (ref "U6") (pin "29") (pinfunction "PA4_29") (pintype "bidirectional"))
    )
    (net (code "106") (name "unconnected-(U6A-PA5-Pad30)") (class "Default")
      (node (ref "U6") (pin "30") (pinfunction "PA5_30") (pintype "bidirectional"))
    )
    (net (code "107") (name "unconnected-(U6A-PA6-Pad31)") (class "Default")
      (node (ref "U6") (pin "31") (pinfunction "PA6_31") (pintype "bidirectional"))
    )
    (net (code "108") (name "unconnected-(U6A-PA7-Pad32)") (class "Default")
      (node (ref "U6") (pin "32") (pinfunction "PA7_32") (pintype "bidirectional"))
    )
    (net (code "109") (name "unconnected-(U6A-PA8-Pad67)") (class "Default")
      (node (ref "U6") (pin "67") (pinfunction "PA8_67") (pintype "bidirectional"))
    )
    (net (code "110") (name "unconnected-(U6A-PA9-Pad68)") (class "Default")
      (node (ref "U6") (pin "68") (pinfunction "PA9_68") (pintype "bidirectional"))
    )
    (net (code "111") (name "unconnected-(U6A-PA10-Pad69)") (class "Default")
      (node (ref "U6") (pin "69") (pinfunction "PA10_69") (pintype "bidirectional"))
    )
    (net (code "112") (name "unconnected-(U6A-PB0-Pad35)") (class "Default")
      (node (ref "U6") (pin "35") (pinfunction "PB0_35") (pintype "bidirectional"))
    )
    (net (code "113") (name "unconnected-(U6A-PB1-Pad36)") (class "Default")
      (node (ref "U6") (pin "36") (pinfunction "PB1_36") (pintype "bidirectional"))
    )
    (net (code "114") (name "unconnected-(U6A-PB4-Pad90)") (class "Default")
      (node (ref "U6") (pin "90") (pinfunction "PB4_90") (pintype "bidirectional"))
    )
    (net (code "115") (name "unconnected-(U6A-PB5-Pad91)") (class "Default")
      (node (ref "U6") (pin "91") (pinfunction "PB5_91") (pintype "bidirectional"))
    )
    (net (code "116") (name "unconnected-(U6A-PB8-Pad95)") (class "Default")
      (node (ref "U6") (pin "95") (pinfunction "PB8_95") (pintype "bidirectional"))
    )
    (net (code "117") (name "unconnected-(U6A-PB12-Pad51)") (class "Default")
      (node (ref "U6") (pin "51") (pinfunction "PB12_51") (pintype "bidirectional"))
    )
    (net (code "118") (name "unconnected-(U6A-PB13-Pad52)") (class "Default")
      (node (ref "U6") (pin "52") (pinfunction "PB13_52") (pintype "bidirectional"))
    )
    (net (code "119") (name "unconnected-(U6A-PB14-Pad53)") (class "Default")
      (node (ref "U6") (pin "53") (pinfunction "PB14_53") (pintype "bidirectional"))
    )
    (net (code "120") (name "unconnected-(U6A-PB15-Pad54)") (class "Default")
      (node (ref "U6") (pin "54") (pinfunction "PB15_54") (pintype "bidirectional"))
    )
    (net (code "121") (name "unconnected-(U6A-PC0-Pad15)") (class "Default")
      (node (ref "U6") (pin "15") (pinfunction "PC0_15") (pintype "bidirectional"))
    )
    (net (code "122") (name "unconnected-(U6A-PC4-Pad33)") (class "Default")
      (node (ref "U6") (pin "33") (pinfunction "PC4_33") (pintype "bidirectional"))
    )
    (net (code "123") (name "unconnected-(U6A-PC5-Pad34)") (class "Default")
      (node (ref "U6") (pin "34") (pinfunction "PC5_34") (pintype "bidirectional"))
    )
    (net (code "124") (name "unconnected-(U6A-PC13-TAMPER-RTC-Pad7)") (class "Default")
      (node (ref "U6") (pin "7") (pinfunction "PC13-TAMPER-RTC_7") (pintype "bidirectional"))
    )
    (net (code "125") (name "unconnected-(U6A-PD6-Pad87)") (class "Default")
      (node (ref "U6") (pin "87") (pinfunction "PD6_87") (pintype "bidirectional"))
    )
    (net (code "126") (name "unconnected-(U6A-PE3-Pad2)") (class "Default")
      (node (ref "U6") (pin "2") (pinfunction "PE3_2") (pintype "bidirectional"))
    )
    (net (code "127") (name "unconnected-(U6A-PE4-Pad3)") (class "Default")
      (node (ref "U6") (pin "3") (pinfunction "PE4_3") (pintype "bidirectional"))
    )
    (net (code "128") (name "unconnected-(U6A-PE5-Pad4)") (class "Default")
      (node (ref "U6") (pin "4") (pinfunction "PE5_4") (pintype "bidirectional"))
    )
    (net (code "129") (name "unconnected-(U6A-PE6-Pad5)") (class "Default")
      (node (ref "U6") (pin "5") (pinfunction "PE6_5") (pintype "bidirectional"))
    )
    (net (code "130") (name "unconnected-(U6B-NC-Pad73)") (class "Default")
      (node (ref "U6") (pin "73") (pinfunction "NC_73") (pintype "passive"))
    )
    (net (code "131") (name "unconnected-(U8-NC-Pad1)") (class "Default")
      (node (ref "U8") (pin "1") (pinfunction "NC_1") (pintype "passive+no_connect"))
    )
    (net (code "132") (name "unconnected-(U8-NC-Pad7)") (class "Default")
      (node (ref "U8") (pin "7") (pinfunction "NC_7") (pintype "passive+no_connect"))
    )
    (net (code "133") (name "unconnected-(U8-NC-Pad8)") (class "Default")
      (node (ref "U8") (pin "8") (pinfunction "NC_8") (pintype "passive+no_connect"))
    )
    (net (code "134") (name "unconnected-(U8-NC-Pad11)") (class "Default")
      (node (ref "U8") (pin "11") (pinfunction "NC_11") (pintype "passive+no_connect"))
    )
    (net (code "135") (name "unconnected-(U8-NC-Pad14)") (class "Default")
      (node (ref "U8") (pin "14") (pinfunction "NC_14") (pintype "passive+no_connect"))
    )
    (net (code "136") (name "unconnected-(U9-NC-Pad3)") (class "Default")
      (node (ref "U9") (pin "3") (pinfunction "NC_3") (pintype "passive+no_connect"))
    )
    (net (code "137") (name "unconnected-(U9-NC-Pad4)") (class "Default")
      (node (ref "U9") (pin "4") (pinfunction "NC_4") (pintype "passive+no_connect"))
    )
    (net (code "138") (name "unconnected-(U9-NC-Pad7)") (class "Default")
      (node (ref "U9") (pin "7") (pinfunction "NC_7") (pintype "passive+no_connect"))
    )
    (net (code "139") (name "unconnected-(U10-SDO-Pad6)") (class "Default")
      (node (ref "U10") (pin "6") (pinfunction "SDO_6") (pintype "passive+no_connect"))
    )
  )
)
